# Noctua.net
KiCad netlist of a schematic drawn in EAGLE
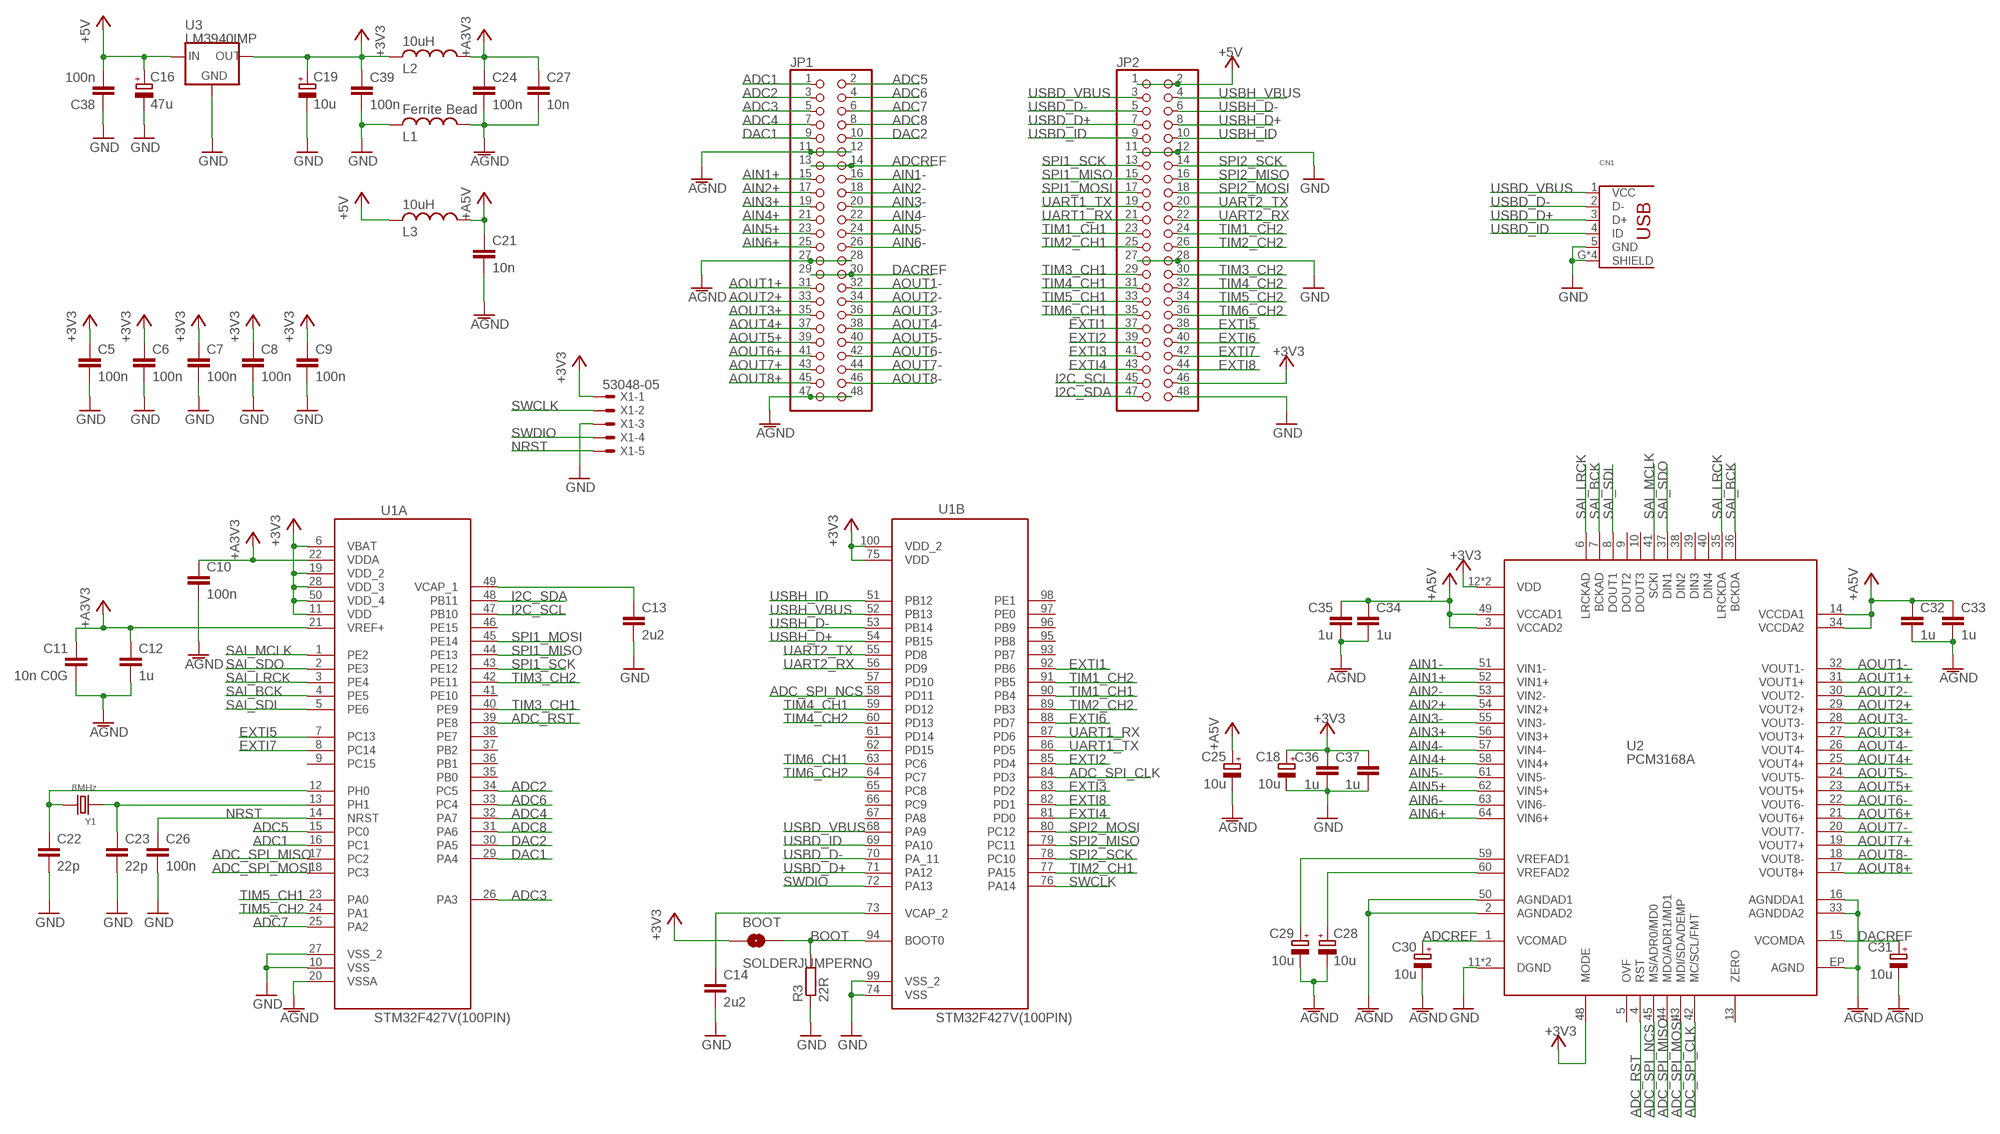
[diagram p0: schematic, sheet 1]

(export (version "E")
  (design (tool "Eeschema 10.0.6"))
  (components
    (comp (ref "BOOT")
      (value "SOLDERJUMPERNO")
      (footprint "eagle-import:SJ_2S-NO")
      (libsource (lib "eagle-import") (part "SOLDERJUMPERNO"))
    )
    (comp (ref "C5")
      (value "100n")
      (footprint "eagle-import:C0603")
      (libsource (lib "eagle-import") (part "C-EUC0603"))
    )
    (comp (ref "C6")
      (value "100n")
      (footprint "eagle-import:C0603")
      (libsource (lib "eagle-import") (part "C-EUC0603"))
    )
    (comp (ref "C7")
      (value "100n")
      (footprint "eagle-import:C0603")
      (libsource (lib "eagle-import") (part "C-EUC0603"))
    )
    (comp (ref "C8")
      (value "100n")
      (footprint "eagle-import:C0603")
      (libsource (lib "eagle-import") (part "C-EUC0603"))
    )
    (comp (ref "C9")
      (value "100n")
      (footprint "eagle-import:C0603")
      (libsource (lib "eagle-import") (part "C-EUC0603"))
    )
    (comp (ref "C10")
      (value "100n")
      (footprint "eagle-import:C0603")
      (libsource (lib "eagle-import") (part "C-EUC0603"))
    )
    (comp (ref "C11")
      (value "10n C0G")
      (footprint "eagle-import:C0603")
      (libsource (lib "eagle-import") (part "C-EUC0603"))
    )
    (comp (ref "C12")
      (value "1u")
      (footprint "eagle-import:C0603")
      (libsource (lib "eagle-import") (part "C-EUC0603"))
    )
    (comp (ref "C13")
      (value "2u2")
      (footprint "eagle-import:C0603")
      (libsource (lib "eagle-import") (part "C-EUC0603"))
    )
    (comp (ref "C14")
      (value "2u2")
      (footprint "eagle-import:C0603")
      (libsource (lib "eagle-import") (part "C-EUC0603"))
    )
    (comp (ref "C16")
      (value "47u")
      (footprint "eagle-import:CPOL-5")
      (libsource (lib "eagle-import") (part "CPOL-EU153CLV-0505"))
    )
    (comp (ref "C18")
      (value "10u")
      (footprint "eagle-import:PANASONIC_B")
      (libsource (lib "eagle-import") (part "CPOL-EUB"))
    )
    (comp (ref "C19")
      (value "10u")
      (footprint "eagle-import:PANASONIC_B")
      (libsource (lib "eagle-import") (part "CPOL-EUB"))
    )
    (comp (ref "C21")
      (value "10n")
      (footprint "eagle-import:C0603")
      (libsource (lib "eagle-import") (part "C-EUC0603"))
    )
    (comp (ref "C22")
      (value "22p")
      (footprint "eagle-import:C0603")
      (libsource (lib "eagle-import") (part "C-EUC0603"))
    )
    (comp (ref "C23")
      (value "22p")
      (footprint "eagle-import:C0603")
      (libsource (lib "eagle-import") (part "C-EUC0603"))
    )
    (comp (ref "C24")
      (value "100n")
      (footprint "eagle-import:C0603")
      (libsource (lib "eagle-import") (part "C-EUC0603"))
    )
    (comp (ref "C25")
      (value "10u")
      (footprint "eagle-import:PANASONIC_B")
      (libsource (lib "eagle-import") (part "CPOL-EUB"))
    )
    (comp (ref "C26")
      (value "100n")
      (footprint "eagle-import:C0603")
      (libsource (lib "eagle-import") (part "C-EUC0603"))
    )
    (comp (ref "C27")
      (value "10n")
      (footprint "eagle-import:C0603")
      (libsource (lib "eagle-import") (part "C-EUC0603"))
    )
    (comp (ref "C28")
      (value "10u")
      (footprint "eagle-import:PANASONIC_B")
      (libsource (lib "eagle-import") (part "CPOL-EUB"))
    )
    (comp (ref "C29")
      (value "10u")
      (footprint "eagle-import:PANASONIC_B")
      (libsource (lib "eagle-import") (part "CPOL-EUB"))
    )
    (comp (ref "C30")
      (value "10u")
      (footprint "eagle-import:PANASONIC_B")
      (libsource (lib "eagle-import") (part "CPOL-EUB"))
    )
    (comp (ref "C31")
      (value "10u")
      (footprint "eagle-import:PANASONIC_B")
      (libsource (lib "eagle-import") (part "CPOL-EUB"))
    )
    (comp (ref "C32")
      (value "1u")
      (footprint "eagle-import:C0603")
      (libsource (lib "eagle-import") (part "C-EUC0603"))
    )
    (comp (ref "C33")
      (value "1u")
      (footprint "eagle-import:C0603")
      (libsource (lib "eagle-import") (part "C-EUC0603"))
    )
    (comp (ref "C34")
      (value "1u")
      (footprint "eagle-import:C0603")
      (libsource (lib "eagle-import") (part "C-EUC0603"))
    )
    (comp (ref "C35")
      (value "1u")
      (footprint "eagle-import:C0603")
      (libsource (lib "eagle-import") (part "C-EUC0603"))
    )
    (comp (ref "C36")
      (value "1u")
      (footprint "eagle-import:C0603")
      (libsource (lib "eagle-import") (part "C-EUC0603"))
    )
    (comp (ref "C37")
      (value "1u")
      (footprint "eagle-import:C0603")
      (libsource (lib "eagle-import") (part "C-EUC0603"))
    )
    (comp (ref "C38")
      (value "100n")
      (footprint "eagle-import:C0603")
      (libsource (lib "eagle-import") (part "C-EUC0603"))
    )
    (comp (ref "C39")
      (value "100n")
      (footprint "eagle-import:C0603")
      (libsource (lib "eagle-import") (part "C-EUC0603"))
    )
    (comp (ref "CN1")
      (value "USB_HRS_ZX62-B-5PA(11)MICRO.B")
      (footprint "eagle-import:HRS_ZX62RD-AB-5P8")
      (libsource (lib "eagle-import") (part "USB_HRS_ZX62-B-5PA(11)MICRO.B"))
    )
    (comp (ref "JP1")
      (value "PINHD-2X24")
      (footprint "eagle-import:2X24")
      (libsource (lib "eagle-import") (part "PINHD-2X24"))
    )
    (comp (ref "JP2")
      (value "PINHD-2X24")
      (footprint "eagle-import:2X24")
      (libsource (lib "eagle-import") (part "PINHD-2X24"))
    )
    (comp (ref "L1")
      (value "Ferrite Bead")
      (footprint "eagle-import:0603")
      (libsource (lib "eagle-import") (part "INDUCTOR"))
    )
    (comp (ref "L2")
      (value "10uH")
      (footprint "eagle-import:0603")
      (libsource (lib "eagle-import") (part "INDUCTOR"))
    )
    (comp (ref "L3")
      (value "10uH")
      (footprint "eagle-import:0603")
      (libsource (lib "eagle-import") (part "INDUCTOR"))
    )
    (comp (ref "R3")
      (value "22R")
      (footprint "eagle-import:0603@1")
      (libsource (lib "eagle-import") (part "R-EU_0603"))
    )
    (comp (ref "U1")
      (value "STM32F427V(100PIN)")
      (footprint "eagle-import:QFP50P1600X1600X160-100N")
      (libsource (lib "eagle-import") (part "STM32F42XV/43XV(100PIN)"))
    )
    (comp (ref "U2")
      (value "PCM3168A")
      (footprint "eagle-import:PQFP64")
      (libsource (lib "eagle-import") (part "PCM3168A"))
    )
    (comp (ref "U3")
      (value "LM3940IMP")
      (footprint "eagle-import:SOT223")
      (libsource (lib "eagle-import") (part "V_REG_LM3940IMP"))
    )
    (comp (ref "X1")
      (value "53048-05")
      (footprint "eagle-import:53048-05")
      (fields (field (name "MF") "MOLEX") (field (name "MPN") "53048-0510"))
      (libsource (lib "eagle-import") (part "53?-05048"))
    )
    (comp (ref "Y1")
      (value "8MHz")
      (footprint "eagle-import:X2-SMD-5.0X3.2X1.3MM")
      (fields (field (name "MPN") "5032/2P"))
      (libsource (lib "eagle-import") (part "SMD-CRYSTAL-8MHZ-20PF-20PPM(2P-5.0X3.2MM)"))
    )
  )
  (nets
    (net (code "1") (name "+3V3") (class "Default")
      (node (ref "BOOT") (pin "1") (pinfunction "1_1") (pintype "passive"))
      (node (ref "C18") (pin "+") (pinfunction "+_+") (pintype "passive"))
      (node (ref "C19") (pin "+") (pinfunction "+_+") (pintype "passive"))
      (node (ref "C36") (pin "1") (pinfunction "1_1") (pintype "passive"))
      (node (ref "C37") (pin "1") (pinfunction "1_1") (pintype "passive"))
      (node (ref "C39") (pin "1") (pinfunction "1_1") (pintype "passive"))
      (node (ref "C5") (pin "1") (pinfunction "1_1") (pintype "passive"))
      (node (ref "C6") (pin "1") (pinfunction "1_1") (pintype "passive"))
      (node (ref "C7") (pin "1") (pinfunction "1_1") (pintype "passive"))
      (node (ref "C8") (pin "1") (pinfunction "1_1") (pintype "passive"))
      (node (ref "C9") (pin "1") (pinfunction "1_1") (pintype "passive"))
      (node (ref "JP2") (pin "46") (pinfunction "46_46") (pintype "passive"))
      (node (ref "L2") (pin "2") (pinfunction "2_2") (pintype "passive"))
      (node (ref "U1") (pin "100") (pinfunction "VDD_2_100") (pintype "bidirectional"))
      (node (ref "U1") (pin "11") (pinfunction "VDD_11") (pintype "bidirectional"))
      (node (ref "U1") (pin "19") (pinfunction "VDD_2_19") (pintype "bidirectional"))
      (node (ref "U1") (pin "28") (pinfunction "VDD_3_28") (pintype "bidirectional"))
      (node (ref "U1") (pin "50") (pinfunction "VDD_4_50") (pintype "bidirectional"))
      (node (ref "U1") (pin "6") (pinfunction "VBAT_6") (pintype "bidirectional"))
      (node (ref "U1") (pin "75") (pinfunction "VDD_75") (pintype "bidirectional"))
      (node (ref "U2") (pin "12") (pinfunction "VDD_12") (pintype "bidirectional"))
      (node (ref "U2") (pin "46") (pinfunction "VDD_46") (pintype "bidirectional"))
      (node (ref "U2") (pin "48") (pinfunction "MODE_48") (pintype "bidirectional"))
      (node (ref "U3") (pin "3") (pinfunction "OUT_3") (pintype "output"))
      (node (ref "X1") (pin "1") (pinfunction "S_1") (pintype "passive"))
    )
    (net (code "2") (name "+5V") (class "Default")
      (node (ref "C16") (pin "+") (pinfunction "+_+") (pintype "passive"))
      (node (ref "C38") (pin "2") (pinfunction "2_2") (pintype "passive"))
      (node (ref "JP2") (pin "1") (pinfunction "1_1") (pintype "passive"))
      (node (ref "JP2") (pin "2") (pinfunction "2_2") (pintype "passive"))
      (node (ref "L3") (pin "2") (pinfunction "2_2") (pintype "passive"))
      (node (ref "U3") (pin "1") (pinfunction "IN_1") (pintype "input"))
    )
    (net (code "3") (name "+A3V3") (class "Default")
      (node (ref "C10") (pin "1") (pinfunction "1_1") (pintype "passive"))
      (node (ref "C11") (pin "1") (pinfunction "1_1") (pintype "passive"))
      (node (ref "C12") (pin "1") (pinfunction "1_1") (pintype "passive"))
      (node (ref "C24") (pin "1") (pinfunction "1_1") (pintype "passive"))
      (node (ref "C27") (pin "1") (pinfunction "1_1") (pintype "passive"))
      (node (ref "L2") (pin "1") (pinfunction "1_1") (pintype "passive"))
      (node (ref "U1") (pin "21") (pinfunction "VREF+_21") (pintype "bidirectional"))
      (node (ref "U1") (pin "22") (pinfunction "VDDA_22") (pintype "bidirectional"))
    )
    (net (code "4") (name "+A5V") (class "Default")
      (node (ref "C21") (pin "1") (pinfunction "1_1") (pintype "passive"))
      (node (ref "C25") (pin "+") (pinfunction "+_+") (pintype "passive"))
      (node (ref "C32") (pin "1") (pinfunction "1_1") (pintype "passive"))
      (node (ref "C33") (pin "1") (pinfunction "1_1") (pintype "passive"))
      (node (ref "C34") (pin "1") (pinfunction "1_1") (pintype "passive"))
      (node (ref "C35") (pin "1") (pinfunction "1_1") (pintype "passive"))
      (node (ref "L3") (pin "1") (pinfunction "1_1") (pintype "passive"))
      (node (ref "U2") (pin "14") (pinfunction "VCCDA1_14") (pintype "bidirectional"))
      (node (ref "U2") (pin "3") (pinfunction "VCCAD2_3") (pintype "bidirectional"))
      (node (ref "U2") (pin "34") (pinfunction "VCCDA2_34") (pintype "bidirectional"))
      (node (ref "U2") (pin "49") (pinfunction "VCCAD1_49") (pintype "bidirectional"))
    )
    (net (code "5") (name "/ADC1") (class "Default")
      (node (ref "JP1") (pin "1") (pinfunction "1_1") (pintype "passive"))
      (node (ref "U1") (pin "16") (pinfunction "PC1_16") (pintype "bidirectional"))
    )
    (net (code "6") (name "/ADC2") (class "Default")
      (node (ref "JP1") (pin "3") (pinfunction "3_3") (pintype "passive"))
      (node (ref "U1") (pin "34") (pinfunction "PC5_34") (pintype "bidirectional"))
    )
    (net (code "7") (name "/ADC3") (class "Default")
      (node (ref "JP1") (pin "5") (pinfunction "5_5") (pintype "passive"))
      (node (ref "U1") (pin "26") (pinfunction "PA3_26") (pintype "bidirectional"))
    )
    (net (code "8") (name "/ADC4") (class "Default")
      (node (ref "JP1") (pin "7") (pinfunction "7_7") (pintype "passive"))
      (node (ref "U1") (pin "32") (pinfunction "PA7_32") (pintype "bidirectional"))
    )
    (net (code "9") (name "/ADC5") (class "Default")
      (node (ref "JP1") (pin "2") (pinfunction "2_2") (pintype "passive"))
      (node (ref "U1") (pin "15") (pinfunction "PC0_15") (pintype "bidirectional"))
    )
    (net (code "10") (name "/ADC6") (class "Default")
      (node (ref "JP1") (pin "4") (pinfunction "4_4") (pintype "passive"))
      (node (ref "U1") (pin "33") (pinfunction "PC4_33") (pintype "bidirectional"))
    )
    (net (code "11") (name "/ADC7") (class "Default")
      (node (ref "JP1") (pin "6") (pinfunction "6_6") (pintype "passive"))
      (node (ref "U1") (pin "25") (pinfunction "PA2_25") (pintype "bidirectional"))
    )
    (net (code "12") (name "/ADC8") (class "Default")
      (node (ref "JP1") (pin "8") (pinfunction "8_8") (pintype "passive"))
      (node (ref "U1") (pin "31") (pinfunction "PA6_31") (pintype "bidirectional"))
    )
    (net (code "13") (name "/ADCREF") (class "Default")
      (node (ref "C30") (pin "+") (pinfunction "+_+") (pintype "passive"))
      (node (ref "JP1") (pin "13") (pinfunction "13_13") (pintype "passive"))
      (node (ref "JP1") (pin "14") (pinfunction "14_14") (pintype "passive"))
      (node (ref "U2") (pin "1") (pinfunction "VCOMAD_1") (pintype "bidirectional"))
    )
    (net (code "14") (name "/ADC_RST") (class "Default")
      (node (ref "U1") (pin "39") (pinfunction "PE8_39") (pintype "bidirectional"))
      (node (ref "U2") (pin "4") (pinfunction "RST_4") (pintype "bidirectional"))
    )
    (net (code "15") (name "/ADC_SPI_CLK") (class "Default")
      (node (ref "U1") (pin "84") (pinfunction "PD3_84") (pintype "bidirectional"))
      (node (ref "U2") (pin "42") (pinfunction "MC/SCL/FMT_42") (pintype "bidirectional"))
    )
    (net (code "16") (name "/ADC_SPI_MISO") (class "Default")
      (node (ref "U1") (pin "17") (pinfunction "PC2_17") (pintype "bidirectional"))
      (node (ref "U2") (pin "44") (pinfunction "MDO/ADR1/MD1_44") (pintype "bidirectional"))
    )
    (net (code "17") (name "/ADC_SPI_MOSI") (class "Default")
      (node (ref "U1") (pin "18") (pinfunction "PC3_18") (pintype "bidirectional"))
      (node (ref "U2") (pin "43") (pinfunction "MDI/SDA/DEMP_43") (pintype "bidirectional"))
    )
    (net (code "18") (name "/ADC_SPI_NCS") (class "Default")
      (node (ref "U1") (pin "58") (pinfunction "PD11_58") (pintype "bidirectional"))
      (node (ref "U2") (pin "45") (pinfunction "MS/ADR0/MD0_45") (pintype "bidirectional"))
    )
    (net (code "19") (name "/AIN1+") (class "Default")
      (node (ref "JP1") (pin "15") (pinfunction "15_15") (pintype "passive"))
      (node (ref "U2") (pin "52") (pinfunction "VIN1+_52") (pintype "bidirectional"))
    )
    (net (code "20") (name "/AIN1-") (class "Default")
      (node (ref "JP1") (pin "16") (pinfunction "16_16") (pintype "passive"))
      (node (ref "U2") (pin "51") (pinfunction "VIN1-_51") (pintype "bidirectional"))
    )
    (net (code "21") (name "/AIN2+") (class "Default")
      (node (ref "JP1") (pin "17") (pinfunction "17_17") (pintype "passive"))
      (node (ref "U2") (pin "54") (pinfunction "VIN2+_54") (pintype "bidirectional"))
    )
    (net (code "22") (name "/AIN2-") (class "Default")
      (node (ref "JP1") (pin "18") (pinfunction "18_18") (pintype "passive"))
      (node (ref "U2") (pin "53") (pinfunction "VIN2-_53") (pintype "bidirectional"))
    )
    (net (code "23") (name "/AIN3+") (class "Default")
      (node (ref "JP1") (pin "19") (pinfunction "19_19") (pintype "passive"))
      (node (ref "U2") (pin "56") (pinfunction "VIN3+_56") (pintype "bidirectional"))
    )
    (net (code "24") (name "/AIN3-") (class "Default")
      (node (ref "JP1") (pin "20") (pinfunction "20_20") (pintype "passive"))
      (node (ref "U2") (pin "55") (pinfunction "VIN3-_55") (pintype "bidirectional"))
    )
    (net (code "25") (name "/AIN4+") (class "Default")
      (node (ref "JP1") (pin "21") (pinfunction "21_21") (pintype "passive"))
      (node (ref "U2") (pin "58") (pinfunction "VIN4+_58") (pintype "bidirectional"))
    )
    (net (code "26") (name "/AIN4-") (class "Default")
      (node (ref "JP1") (pin "22") (pinfunction "22_22") (pintype "passive"))
      (node (ref "U2") (pin "57") (pinfunction "VIN4-_57") (pintype "bidirectional"))
    )
    (net (code "27") (name "/AIN5+") (class "Default")
      (node (ref "JP1") (pin "23") (pinfunction "23_23") (pintype "passive"))
      (node (ref "U2") (pin "62") (pinfunction "VIN5+_62") (pintype "bidirectional"))
    )
    (net (code "28") (name "/AIN5-") (class "Default")
      (node (ref "JP1") (pin "24") (pinfunction "24_24") (pintype "passive"))
      (node (ref "U2") (pin "61") (pinfunction "VIN5-_61") (pintype "bidirectional"))
    )
    (net (code "29") (name "/AIN6+") (class "Default")
      (node (ref "JP1") (pin "25") (pinfunction "25_25") (pintype "passive"))
      (node (ref "U2") (pin "64") (pinfunction "VIN6+_64") (pintype "bidirectional"))
    )
    (net (code "30") (name "/AIN6-") (class "Default")
      (node (ref "JP1") (pin "26") (pinfunction "26_26") (pintype "passive"))
      (node (ref "U2") (pin "63") (pinfunction "VIN6-_63") (pintype "bidirectional"))
    )
    (net (code "31") (name "/AOUT1+") (class "Default")
      (node (ref "JP1") (pin "31") (pinfunction "31_31") (pintype "passive"))
      (node (ref "U2") (pin "31") (pinfunction "VOUT1+_31") (pintype "bidirectional"))
    )
    (net (code "32") (name "/AOUT1-") (class "Default")
      (node (ref "JP1") (pin "32") (pinfunction "32_32") (pintype "passive"))
      (node (ref "U2") (pin "32") (pinfunction "VOUT1-_32") (pintype "bidirectional"))
    )
    (net (code "33") (name "/AOUT2+") (class "Default")
      (node (ref "JP1") (pin "33") (pinfunction "33_33") (pintype "passive"))
      (node (ref "U2") (pin "29") (pinfunction "VOUT2+_29") (pintype "bidirectional"))
    )
    (net (code "34") (name "/AOUT2-") (class "Default")
      (node (ref "JP1") (pin "34") (pinfunction "34_34") (pintype "passive"))
      (node (ref "U2") (pin "30") (pinfunction "VOUT2-_30") (pintype "bidirectional"))
    )
    (net (code "35") (name "/AOUT3+") (class "Default")
      (node (ref "JP1") (pin "35") (pinfunction "35_35") (pintype "passive"))
      (node (ref "U2") (pin "27") (pinfunction "VOUT3+_27") (pintype "bidirectional"))
    )
    (net (code "36") (name "/AOUT3-") (class "Default")
      (node (ref "JP1") (pin "36") (pinfunction "36_36") (pintype "passive"))
      (node (ref "U2") (pin "28") (pinfunction "VOUT3-_28") (pintype "bidirectional"))
    )
    (net (code "37") (name "/AOUT4+") (class "Default")
      (node (ref "JP1") (pin "37") (pinfunction "37_37") (pintype "passive"))
      (node (ref "U2") (pin "25") (pinfunction "VOUT4+_25") (pintype "bidirectional"))
    )
    (net (code "38") (name "/AOUT4-") (class "Default")
      (node (ref "JP1") (pin "38") (pinfunction "38_38") (pintype "passive"))
      (node (ref "U2") (pin "26") (pinfunction "VOUT4-_26") (pintype "bidirectional"))
    )
    (net (code "39") (name "/AOUT5+") (class "Default")
      (node (ref "JP1") (pin "39") (pinfunction "39_39") (pintype "passive"))
      (node (ref "U2") (pin "23") (pinfunction "VOUT5+_23") (pintype "bidirectional"))
    )
    (net (code "40") (name "/AOUT5-") (class "Default")
      (node (ref "JP1") (pin "40") (pinfunction "40_40") (pintype "passive"))
      (node (ref "U2") (pin "24") (pinfunction "VOUT5-_24") (pintype "bidirectional"))
    )
    (net (code "41") (name "/AOUT6+") (class "Default")
      (node (ref "JP1") (pin "41") (pinfunction "41_41") (pintype "passive"))
      (node (ref "U2") (pin "21") (pinfunction "VOUT6+_21") (pintype "bidirectional"))
    )
    (net (code "42") (name "/AOUT6-") (class "Default")
      (node (ref "JP1") (pin "42") (pinfunction "42_42") (pintype "passive"))
      (node (ref "U2") (pin "22") (pinfunction "VOUT6-_22") (pintype "bidirectional"))
    )
    (net (code "43") (name "/AOUT7+") (class "Default")
      (node (ref "JP1") (pin "43") (pinfunction "43_43") (pintype "passive"))
      (node (ref "U2") (pin "19") (pinfunction "VOUT7+_19") (pintype "bidirectional"))
    )
    (net (code "44") (name "/AOUT7-") (class "Default")
      (node (ref "JP1") (pin "44") (pinfunction "44_44") (pintype "passive"))
      (node (ref "U2") (pin "20") (pinfunction "VOUT7-_20") (pintype "bidirectional"))
    )
    (net (code "45") (name "/AOUT8+") (class "Default")
      (node (ref "JP1") (pin "45") (pinfunction "45_45") (pintype "passive"))
      (node (ref "U2") (pin "17") (pinfunction "VOUT8+_17") (pintype "bidirectional"))
    )
    (net (code "46") (name "/AOUT8-") (class "Default")
      (node (ref "JP1") (pin "46") (pinfunction "46_46") (pintype "passive"))
      (node (ref "U2") (pin "18") (pinfunction "VOUT8-_18") (pintype "bidirectional"))
    )
    (net (code "47") (name "/BOOT") (class "Default")
      (node (ref "BOOT") (pin "2") (pinfunction "2_2") (pintype "passive"))
      (node (ref "R3") (pin "2") (pinfunction "2_2") (pintype "passive"))
      (node (ref "U1") (pin "94") (pinfunction "BOOT0_94") (pintype "bidirectional"))
    )
    (net (code "48") (name "/DAC1") (class "Default")
      (node (ref "JP1") (pin "9") (pinfunction "9_9") (pintype "passive"))
      (node (ref "U1") (pin "29") (pinfunction "PA4_29") (pintype "bidirectional"))
    )
    (net (code "49") (name "/DAC2") (class "Default")
      (node (ref "JP1") (pin "10") (pinfunction "10_10") (pintype "passive"))
      (node (ref "U1") (pin "30") (pinfunction "PA5_30") (pintype "bidirectional"))
    )
    (net (code "50") (name "/DACREF") (class "Default")
      (node (ref "C31") (pin "+") (pinfunction "+_+") (pintype "passive"))
      (node (ref "JP1") (pin "29") (pinfunction "29_29") (pintype "passive"))
      (node (ref "JP1") (pin "30") (pinfunction "30_30") (pintype "passive"))
      (node (ref "U2") (pin "15") (pinfunction "VCOMDA_15") (pintype "bidirectional"))
    )
    (net (code "51") (name "/EXTI1") (class "Default")
      (node (ref "JP2") (pin "37") (pinfunction "37_37") (pintype "passive"))
      (node (ref "U1") (pin "92") (pinfunction "PB6_92") (pintype "bidirectional"))
    )
    (net (code "52") (name "/EXTI2") (class "Default")
      (node (ref "JP2") (pin "39") (pinfunction "39_39") (pintype "passive"))
      (node (ref "U1") (pin "85") (pinfunction "PD4_85") (pintype "bidirectional"))
    )
    (net (code "53") (name "/EXTI3") (class "Default")
      (node (ref "JP2") (pin "41") (pinfunction "41_41") (pintype "passive"))
      (node (ref "U1") (pin "83") (pinfunction "PD2_83") (pintype "bidirectional"))
    )
    (net (code "54") (name "/EXTI4") (class "Default")
      (node (ref "JP2") (pin "43") (pinfunction "43_43") (pintype "passive"))
      (node (ref "U1") (pin "81") (pinfunction "PD0_81") (pintype "bidirectional"))
    )
    (net (code "55") (name "/EXTI5") (class "Default")
      (node (ref "JP2") (pin "38") (pinfunction "38_38") (pintype "passive"))
      (node (ref "U1") (pin "7") (pinfunction "PC13_7") (pintype "bidirectional"))
    )
    (net (code "56") (name "/EXTI6") (class "Default")
      (node (ref "JP2") (pin "40") (pinfunction "40_40") (pintype "passive"))
      (node (ref "U1") (pin "88") (pinfunction "PD7_88") (pintype "bidirectional"))
    )
    (net (code "57") (name "/EXTI7") (class "Default")
      (node (ref "JP2") (pin "42") (pinfunction "42_42") (pintype "passive"))
      (node (ref "U1") (pin "8") (pinfunction "PC14_8") (pintype "bidirectional"))
    )
    (net (code "58") (name "/EXTI8") (class "Default")
      (node (ref "JP2") (pin "44") (pinfunction "44_44") (pintype "passive"))
      (node (ref "U1") (pin "82") (pinfunction "PD1_82") (pintype "bidirectional"))
    )
    (net (code "59") (name "/I2C_SCL") (class "Default")
      (node (ref "JP2") (pin "45") (pinfunction "45_45") (pintype "passive"))
      (node (ref "U1") (pin "47") (pinfunction "PB10_47") (pintype "bidirectional"))
    )
    (net (code "60") (name "/I2C_SDA") (class "Default")
      (node (ref "JP2") (pin "47") (pinfunction "47_47") (pintype "passive"))
      (node (ref "U1") (pin "48") (pinfunction "PB11_48") (pintype "bidirectional"))
    )
    (net (code "61") (name "/NRST") (class "Default")
      (node (ref "C26") (pin "1") (pinfunction "1_1") (pintype "passive"))
      (node (ref "U1") (pin "14") (pinfunction "NRST_14") (pintype "bidirectional"))
      (node (ref "X1") (pin "5") (pinfunction "S_5") (pintype "passive"))
    )
    (net (code "62") (name "/SAI_BCK") (class "Default")
      (node (ref "U1") (pin "4") (pinfunction "PE5_4") (pintype "bidirectional"))
      (node (ref "U2") (pin "36") (pinfunction "BCKDA_36") (pintype "bidirectional"))
      (node (ref "U2") (pin "7") (pinfunction "BCKAD_7") (pintype "bidirectional"))
    )
    (net (code "63") (name "/SAI_LRCK") (class "Default")
      (node (ref "U1") (pin "3") (pinfunction "PE4_3") (pintype "bidirectional"))
      (node (ref "U2") (pin "35") (pinfunction "LRCKDA_35") (pintype "bidirectional"))
      (node (ref "U2") (pin "6") (pinfunction "LRCKAD_6") (pintype "bidirectional"))
    )
    (net (code "64") (name "/SAI_MCLK") (class "Default")
      (node (ref "U1") (pin "1") (pinfunction "PE2_1") (pintype "bidirectional"))
      (node (ref "U2") (pin "41") (pinfunction "SCKI_41") (pintype "bidirectional"))
    )
    (net (code "65") (name "/SAI_SDI") (class "Default")
      (node (ref "U1") (pin "5") (pinfunction "PE6_5") (pintype "bidirectional"))
      (node (ref "U2") (pin "8") (pinfunction "DOUT1_8") (pintype "bidirectional"))
    )
    (net (code "66") (name "/SAI_SDO") (class "Default")
      (node (ref "U1") (pin "2") (pinfunction "PE3_2") (pintype "bidirectional"))
      (node (ref "U2") (pin "37") (pinfunction "DIN1_37") (pintype "bidirectional"))
    )
    (net (code "67") (name "/SPI1_MISO") (class "Default")
      (node (ref "JP2") (pin "15") (pinfunction "15_15") (pintype "passive"))
      (node (ref "U1") (pin "44") (pinfunction "PE13_44") (pintype "bidirectional"))
    )
    (net (code "68") (name "/SPI1_MOSI") (class "Default")
      (node (ref "JP2") (pin "17") (pinfunction "17_17") (pintype "passive"))
      (node (ref "U1") (pin "45") (pinfunction "PE14_45") (pintype "bidirectional"))
    )
    (net (code "69") (name "/SPI1_SCK") (class "Default")
      (node (ref "JP2") (pin "13") (pinfunction "13_13") (pintype "passive"))
      (node (ref "U1") (pin "43") (pinfunction "PE12_43") (pintype "bidirectional"))
    )
    (net (code "70") (name "/SPI2_MISO") (class "Default")
      (node (ref "JP2") (pin "16") (pinfunction "16_16") (pintype "passive"))
      (node (ref "U1") (pin "79") (pinfunction "PC11_79") (pintype "bidirectional"))
    )
    (net (code "71") (name "/SPI2_MOSI") (class "Default")
      (node (ref "JP2") (pin "18") (pinfunction "18_18") (pintype "passive"))
      (node (ref "U1") (pin "80") (pinfunction "PC12_80") (pintype "bidirectional"))
    )
    (net (code "72") (name "/SPI2_SCK") (class "Default")
      (node (ref "JP2") (pin "14") (pinfunction "14_14") (pintype "passive"))
      (node (ref "U1") (pin "78") (pinfunction "PC10_78") (pintype "bidirectional"))
    )
    (net (code "73") (name "/SWCLK") (class "Default")
      (node (ref "U1") (pin "76") (pinfunction "PA14_76") (pintype "bidirectional"))
      (node (ref "X1") (pin "2") (pinfunction "S_2") (pintype "passive"))
    )
    (net (code "74") (name "/SWDIO") (class "Default")
      (node (ref "U1") (pin "72") (pinfunction "PA13_72") (pintype "bidirectional"))
      (node (ref "X1") (pin "4") (pinfunction "S_4") (pintype "passive"))
    )
    (net (code "75") (name "/TIM1_CH1") (class "Default")
      (node (ref "JP2") (pin "23") (pinfunction "23_23") (pintype "passive"))
      (node (ref "U1") (pin "90") (pinfunction "PB4_90") (pintype "bidirectional"))
    )
    (net (code "76") (name "/TIM1_CH2") (class "Default")
      (node (ref "JP2") (pin "24") (pinfunction "24_24") (pintype "passive"))
      (node (ref "U1") (pin "91") (pinfunction "PB5_91") (pintype "bidirectional"))
    )
    (net (code "77") (name "/TIM2_CH1") (class "Default")
      (node (ref "JP2") (pin "25") (pinfunction "25_25") (pintype "passive"))
      (node (ref "U1") (pin "77") (pinfunction "PA15_77") (pintype "bidirectional"))
    )
    (net (code "78") (name "/TIM2_CH2") (class "Default")
      (node (ref "JP2") (pin "26") (pinfunction "26_26") (pintype "passive"))
      (node (ref "U1") (pin "89") (pinfunction "PB3_89") (pintype "bidirectional"))
    )
    (net (code "79") (name "/TIM3_CH1") (class "Default")
      (node (ref "JP2") (pin "29") (pinfunction "29_29") (pintype "passive"))
      (node (ref "U1") (pin "40") (pinfunction "PE9_40") (pintype "bidirectional"))
    )
    (net (code "80") (name "/TIM3_CH2") (class "Default")
      (node (ref "JP2") (pin "30") (pinfunction "30_30") (pintype "passive"))
      (node (ref "U1") (pin "42") (pinfunction "PE11_42") (pintype "bidirectional"))
    )
    (net (code "81") (name "/TIM4_CH1") (class "Default")
      (node (ref "JP2") (pin "31") (pinfunction "31_31") (pintype "passive"))
      (node (ref "U1") (pin "59") (pinfunction "PD12_59") (pintype "bidirectional"))
    )
    (net (code "82") (name "/TIM4_CH2") (class "Default")
      (node (ref "JP2") (pin "32") (pinfunction "32_32") (pintype "passive"))
      (node (ref "U1") (pin "60") (pinfunction "PD13_60") (pintype "bidirectional"))
    )
    (net (code "83") (name "/TIM5_CH1") (class "Default")
      (node (ref "JP2") (pin "33") (pinfunction "33_33") (pintype "passive"))
      (node (ref "U1") (pin "23") (pinfunction "PA0_23") (pintype "bidirectional"))
    )
    (net (code "84") (name "/TIM5_CH2") (class "Default")
      (node (ref "JP2") (pin "34") (pinfunction "34_34") (pintype "passive"))
      (node (ref "U1") (pin "24") (pinfunction "PA1_24") (pintype "bidirectional"))
    )
    (net (code "85") (name "/TIM6_CH1") (class "Default")
      (node (ref "JP2") (pin "35") (pinfunction "35_35") (pintype "passive"))
      (node (ref "U1") (pin "63") (pinfunction "PC6_63") (pintype "bidirectional"))
    )
    (net (code "86") (name "/TIM6_CH2") (class "Default")
      (node (ref "JP2") (pin "36") (pinfunction "36_36") (pintype "passive"))
      (node (ref "U1") (pin "64") (pinfunction "PC7_64") (pintype "bidirectional"))
    )
    (net (code "87") (name "/UART1_RX") (class "Default")
      (node (ref "JP2") (pin "21") (pinfunction "21_21") (pintype "passive"))
      (node (ref "U1") (pin "87") (pinfunction "PD6_87") (pintype "bidirectional"))
    )
    (net (code "88") (name "/UART1_TX") (class "Default")
      (node (ref "JP2") (pin "19") (pinfunction "19_19") (pintype "passive"))
      (node (ref "U1") (pin "86") (pinfunction "PD5_86") (pintype "bidirectional"))
    )
    (net (code "89") (name "/UART2_RX") (class "Default")
      (node (ref "JP2") (pin "22") (pinfunction "22_22") (pintype "passive"))
      (node (ref "U1") (pin "56") (pinfunction "PD9_56") (pintype "bidirectional"))
    )
    (net (code "90") (name "/UART2_TX") (class "Default")
      (node (ref "JP2") (pin "20") (pinfunction "20_20") (pintype "passive"))
      (node (ref "U1") (pin "55") (pinfunction "PD8_55") (pintype "bidirectional"))
    )
    (net (code "91") (name "/USBD_D+") (class "Default")
      (node (ref "CN1") (pin "3") (pinfunction "D+_3") (pintype "bidirectional"))
      (node (ref "JP2") (pin "7") (pinfunction "7_7") (pintype "passive"))
      (node (ref "U1") (pin "71") (pinfunction "PA12_71") (pintype "bidirectional"))
    )
    (net (code "92") (name "/USBD_D-") (class "Default")
      (node (ref "CN1") (pin "2") (pinfunction "D-_2") (pintype "bidirectional"))
      (node (ref "JP2") (pin "5") (pinfunction "5_5") (pintype "passive"))
      (node (ref "U1") (pin "70") (pinfunction "PA_11_70") (pintype "bidirectional"))
    )
    (net (code "93") (name "/USBD_ID") (class "Default")
      (node (ref "CN1") (pin "4") (pinfunction "ID_4") (pintype "bidirectional"))
      (node (ref "JP2") (pin "9") (pinfunction "9_9") (pintype "passive"))
      (node (ref "U1") (pin "69") (pinfunction "PA10_69") (pintype "bidirectional"))
    )
    (net (code "94") (name "/USBD_VBUS") (class "Default")
      (node (ref "CN1") (pin "1") (pinfunction "VCC_1") (pintype "bidirectional"))
      (node (ref "JP2") (pin "3") (pinfunction "3_3") (pintype "passive"))
      (node (ref "U1") (pin "68") (pinfunction "PA9_68") (pintype "bidirectional"))
    )
    (net (code "95") (name "/USBH_D+") (class "Default")
      (node (ref "JP2") (pin "8") (pinfunction "8_8") (pintype "passive"))
      (node (ref "U1") (pin "54") (pinfunction "PB15_54") (pintype "bidirectional"))
    )
    (net (code "96") (name "/USBH_D-") (class "Default")
      (node (ref "JP2") (pin "6") (pinfunction "6_6") (pintype "passive"))
      (node (ref "U1") (pin "53") (pinfunction "PB14_53") (pintype "bidirectional"))
    )
    (net (code "97") (name "/USBH_ID") (class "Default")
      (node (ref "JP2") (pin "10") (pinfunction "10_10") (pintype "passive"))
      (node (ref "U1") (pin "51") (pinfunction "PB12_51") (pintype "bidirectional"))
    )
    (net (code "98") (name "/USBH_VBUS") (class "Default")
      (node (ref "JP2") (pin "4") (pinfunction "4_4") (pintype "passive"))
      (node (ref "U1") (pin "52") (pinfunction "PB13_52") (pintype "bidirectional"))
    )
    (net (code "99") (name "AGND") (class "Default")
      (node (ref "C10") (pin "2") (pinfunction "2_2") (pintype "passive"))
      (node (ref "C11") (pin "2") (pinfunction "2_2") (pintype "passive"))
      (node (ref "C12") (pin "2") (pinfunction "2_2") (pintype "passive"))
      (node (ref "C21") (pin "2") (pinfunction "2_2") (pintype "passive"))
      (node (ref "C24") (pin "2") (pinfunction "2_2") (pintype "passive"))
      (node (ref "C25") (pin "-") (pinfunction "-_-") (pintype "passive"))
      (node (ref "C27") (pin "2") (pinfunction "2_2") (pintype "passive"))
      (node (ref "C28") (pin "-") (pinfunction "-_-") (pintype "passive"))
      (node (ref "C29") (pin "-") (pinfunction "-_-") (pintype "passive"))
      (node (ref "C30") (pin "-") (pinfunction "-_-") (pintype "passive"))
      (node (ref "C31") (pin "-") (pinfunction "-_-") (pintype "passive"))
      (node (ref "C32") (pin "2") (pinfunction "2_2") (pintype "passive"))
      (node (ref "C33") (pin "2") (pinfunction "2_2") (pintype "passive"))
      (node (ref "C34") (pin "2") (pinfunction "2_2") (pintype "passive"))
      (node (ref "C35") (pin "2") (pinfunction "2_2") (pintype "passive"))
      (node (ref "JP1") (pin "11") (pinfunction "11_11") (pintype "passive"))
      (node (ref "JP1") (pin "12") (pinfunction "12_12") (pintype "passive"))
      (node (ref "JP1") (pin "27") (pinfunction "27_27") (pintype "passive"))
      (node (ref "JP1") (pin "28") (pinfunction "28_28") (pintype "passive"))
      (node (ref "JP1") (pin "47") (pinfunction "47_47") (pintype "passive"))
      (node (ref "JP1") (pin "48") (pinfunction "48_48") (pintype "passive"))
      (node (ref "L1") (pin "1") (pinfunction "1_1") (pintype "passive"))
      (node (ref "U1") (pin "20") (pinfunction "VSSA_20") (pintype "bidirectional"))
      (node (ref "U2") (pin "16") (pinfunction "AGNDDA1_16") (pintype "bidirectional"))
      (node (ref "U2") (pin "2") (pinfunction "AGNDAD2_2") (pintype "bidirectional"))
      (node (ref "U2") (pin "33") (pinfunction "AGNDDA2_33") (pintype "bidirectional"))
      (node (ref "U2") (pin "50") (pinfunction "AGNDAD1_50") (pintype "bidirectional"))
      (node (ref "U2") (pin "EP") (pinfunction "AGND_EP") (pintype "bidirectional"))
    )
    (net (code "100") (name "GND") (class "Default")
      (node (ref "C13") (pin "2") (pinfunction "2_2") (pintype "passive"))
      (node (ref "C14") (pin "2") (pinfunction "2_2") (pintype "passive"))
      (node (ref "C16") (pin "-") (pinfunction "-_-") (pintype "passive"))
      (node (ref "C18") (pin "-") (pinfunction "-_-") (pintype "passive"))
      (node (ref "C19") (pin "-") (pinfunction "-_-") (pintype "passive"))
      (node (ref "C22") (pin "2") (pinfunction "2_2") (pintype "passive"))
      (node (ref "C23") (pin "2") (pinfunction "2_2") (pintype "passive"))
      (node (ref "C26") (pin "2") (pinfunction "2_2") (pintype "passive"))
      (node (ref "C36") (pin "2") (pinfunction "2_2") (pintype "passive"))
      (node (ref "C37") (pin "2") (pinfunction "2_2") (pintype "passive"))
      (node (ref "C38") (pin "1") (pinfunction "1_1") (pintype "passive"))
      (node (ref "C39") (pin "2") (pinfunction "2_2") (pintype "passive"))
      (node (ref "C5") (pin "2") (pinfunction "2_2") (pintype "passive"))
      (node (ref "C6") (pin "2") (pinfunction "2_2") (pintype "passive"))
      (node (ref "C7") (pin "2") (pinfunction "2_2") (pintype "passive"))
      (node (ref "C8") (pin "2") (pinfunction "2_2") (pintype "passive"))
      (node (ref "C9") (pin "2") (pinfunction "2_2") (pintype "passive"))
      (node (ref "CN1") (pin "5") (pinfunction "GND_5") (pintype "bidirectional"))
      (node (ref "CN1") (pin "G") (pinfunction "SHIELD_G") (pintype "bidirectional"))
      (node (ref "CN1") (pin "G2") (pinfunction "SHIELD_G2") (pintype "bidirectional"))
      (node (ref "CN1") (pin "G3") (pinfunction "SHIELD_G3") (pintype "bidirectional"))
      (node (ref "CN1") (pin "G4") (pinfunction "SHIELD_G4") (pintype "bidirectional"))
      (node (ref "JP2") (pin "11") (pinfunction "11_11") (pintype "passive"))
      (node (ref "JP2") (pin "12") (pinfunction "12_12") (pintype "passive"))
      (node (ref "JP2") (pin "27") (pinfunction "27_27") (pintype "passive"))
      (node (ref "JP2") (pin "28") (pinfunction "28_28") (pintype "passive"))
      (node (ref "JP2") (pin "48") (pinfunction "48_48") (pintype "passive"))
      (node (ref "L1") (pin "2") (pinfunction "2_2") (pintype "passive"))
      (node (ref "R3") (pin "1") (pinfunction "1_1") (pintype "passive"))
      (node (ref "U1") (pin "10") (pinfunction "VSS_10") (pintype "bidirectional"))
      (node (ref "U1") (pin "27") (pinfunction "VSS_2_27") (pintype "bidirectional"))
      (node (ref "U1") (pin "74") (pinfunction "VSS_74") (pintype "bidirectional"))
      (node (ref "U1") (pin "99") (pinfunction "VSS_2_99") (pintype "bidirectional"))
      (node (ref "U2") (pin "11") (pinfunction "DGND_11") (pintype "bidirectional"))
      (node (ref "U2") (pin "47") (pinfunction "DGND_47") (pintype "bidirectional"))
      (node (ref "U3") (pin "2") (pinfunction "GND_2") (pintype "input"))
      (node (ref "X1") (pin "3") (pinfunction "S_3") (pintype "passive"))
    )
    (net (code "101") (name "Net-(U1A-PH0)") (class "Default")
      (node (ref "C22") (pin "1") (pinfunction "1_1") (pintype "passive"))
      (node (ref "U1") (pin "12") (pinfunction "PH0_12") (pintype "bidirectional"))
      (node (ref "Y1") (pin "2") (pinfunction "2_2") (pintype "passive"))
    )
    (net (code "102") (name "Net-(U1A-PH1)") (class "Default")
      (node (ref "C23") (pin "1") (pinfunction "1_1") (pintype "passive"))
      (node (ref "U1") (pin "13") (pinfunction "PH1_13") (pintype "bidirectional"))
      (node (ref "Y1") (pin "1") (pinfunction "1_1") (pintype "passive"))
    )
    (net (code "103") (name "Net-(U1A-VCAP_1)") (class "Default")
      (node (ref "C13") (pin "1") (pinfunction "1_1") (pintype "passive"))
      (node (ref "U1") (pin "49") (pinfunction "VCAP_1_49") (pintype "bidirectional"))
    )
    (net (code "104") (name "Net-(U1B-VCAP_2)") (class "Default")
      (node (ref "C14") (pin "1") (pinfunction "1_1") (pintype "passive"))
      (node (ref "U1") (pin "73") (pinfunction "VCAP_2_73") (pintype "bidirectional"))
    )
    (net (code "105") (name "Net-(U2-VREFAD1)") (class "Default")
      (node (ref "C29") (pin "+") (pinfunction "+_+") (pintype "passive"))
      (node (ref "U2") (pin "59") (pinfunction "VREFAD1_59") (pintype "bidirectional"))
    )
    (net (code "106") (name "Net-(U2-VREFAD2)") (class "Default")
      (node (ref "C28") (pin "+") (pinfunction "+_+") (pintype "passive"))
      (node (ref "U2") (pin "60") (pinfunction "VREFAD2_60") (pintype "bidirectional"))
    )
    (net (code "107") (name "unconnected-(U1A-PB0-Pad35)") (class "Default")
      (node (ref "U1") (pin "35") (pinfunction "PB0_35") (pintype "bidirectional"))
    )
    (net (code "108") (name "unconnected-(U1A-PB1-Pad36)") (class "Default")
      (node (ref "U1") (pin "36") (pinfunction "PB1_36") (pintype "bidirectional"))
    )
    (net (code "109") (name "unconnected-(U1A-PB2-Pad37)") (class "Default")
      (node (ref "U1") (pin "37") (pinfunction "PB2_37") (pintype "bidirectional"))
    )
    (net (code "110") (name "unconnected-(U1A-PC15-Pad9)") (class "Default")
      (node (ref "U1") (pin "9") (pinfunction "PC15_9") (pintype "bidirectional"))
    )
    (net (code "111") (name "unconnected-(U1A-PE7-Pad38)") (class "Default")
      (node (ref "U1") (pin "38") (pinfunction "PE7_38") (pintype "bidirectional"))
    )
    (net (code "112") (name "unconnected-(U1A-PE10-Pad41)") (class "Default")
      (node (ref "U1") (pin "41") (pinfunction "PE10_41") (pintype "bidirectional"))
    )
    (net (code "113") (name "unconnected-(U1A-PE15-Pad46)") (class "Default")
      (node (ref "U1") (pin "46") (pinfunction "PE15_46") (pintype "bidirectional"))
    )
    (net (code "114") (name "unconnected-(U1B-PA8-Pad67)") (class "Default")
      (node (ref "U1") (pin "67") (pinfunction "PA8_67") (pintype "bidirectional"))
    )
    (net (code "115") (name "unconnected-(U1B-PB7-Pad93)") (class "Default")
      (node (ref "U1") (pin "93") (pinfunction "PB7_93") (pintype "bidirectional"))
    )
    (net (code "116") (name "unconnected-(U1B-PB8-Pad95)") (class "Default")
      (node (ref "U1") (pin "95") (pinfunction "PB8_95") (pintype "bidirectional"))
    )
    (net (code "117") (name "unconnected-(U1B-PB9-Pad96)") (class "Default")
      (node (ref "U1") (pin "96") (pinfunction "PB9_96") (pintype "bidirectional"))
    )
    (net (code "118") (name "unconnected-(U1B-PC8-Pad65)") (class "Default")
      (node (ref "U1") (pin "65") (pinfunction "PC8_65") (pintype "bidirectional"))
    )
    (net (code "119") (name "unconnected-(U1B-PC9-Pad66)") (class "Default")
      (node (ref "U1") (pin "66") (pinfunction "PC9_66") (pintype "bidirectional"))
    )
    (net (code "120") (name "unconnected-(U1B-PD10-Pad57)") (class "Default")
      (node (ref "U1") (pin "57") (pinfunction "PD10_57") (pintype "bidirectional"))
    )
    (net (code "121") (name "unconnected-(U1B-PD14-Pad61)") (class "Default")
      (node (ref "U1") (pin "61") (pinfunction "PD14_61") (pintype "bidirectional"))
    )
    (net (code "122") (name "unconnected-(U1B-PD15-Pad62)") (class "Default")
      (node (ref "U1") (pin "62") (pinfunction "PD15_62") (pintype "bidirectional"))
    )
    (net (code "123") (name "unconnected-(U1B-PE0-Pad97)") (class "Default")
      (node (ref "U1") (pin "97") (pinfunction "PE0_97") (pintype "bidirectional"))
    )
    (net (code "124") (name "unconnected-(U1B-PE1-Pad98)") (class "Default")
      (node (ref "U1") (pin "98") (pinfunction "PE1_98") (pintype "bidirectional"))
    )
    (net (code "125") (name "unconnected-(U2-DIN2-Pad38)") (class "Default")
      (node (ref "U2") (pin "38") (pinfunction "DIN2_38") (pintype "bidirectional"))
    )
    (net (code "126") (name "unconnected-(U2-DIN3-Pad39)") (class "Default")
      (node (ref "U2") (pin "39") (pinfunction "DIN3_39") (pintype "bidirectional"))
    )
    (net (code "127") (name "unconnected-(U2-DIN4-Pad40)") (class "Default")
      (node (ref "U2") (pin "40") (pinfunction "DIN4_40") (pintype "bidirectional"))
    )
    (net (code "128") (name "unconnected-(U2-DOUT2-Pad9)") (class "Default")
      (node (ref "U2") (pin "9") (pinfunction "DOUT2_9") (pintype "bidirectional"))
    )
    (net (code "129") (name "unconnected-(U2-DOUT3-Pad10)") (class "Default")
      (node (ref "U2") (pin "10") (pinfunction "DOUT3_10") (pintype "bidirectional"))
    )
    (net (code "130") (name "unconnected-(U2-OVF-Pad5)") (class "Default")
      (node (ref "U2") (pin "5") (pinfunction "OVF_5") (pintype "bidirectional"))
    )
    (net (code "131") (name "unconnected-(U2-ZERO-Pad13)") (class "Default")
      (node (ref "U2") (pin "13") (pinfunction "ZERO_13") (pintype "bidirectional"))
    )
  )
)
